# TelephoneConnect.net
KiCad netlist of a schematic drawn in EAGLE
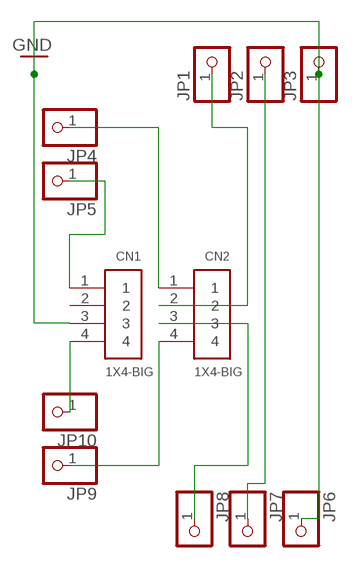
[diagram p0: schematic, sheet 1]

(export (version "E")
  (design (tool "Eeschema 10.0.6"))
  (components
    (comp (ref "CN1")
      (value "1X4-BIG")
      (footprint "eagle-import:1X04-BIG")
      (libsource (lib "eagle-import") (part "1X4-BIG"))
    )
    (comp (ref "CN2")
      (value "1X4-BIG")
      (footprint "eagle-import:1X04-BIG")
      (libsource (lib "eagle-import") (part "1X4-BIG"))
    )
    (comp (ref "JP1")
      (value "PINHD-1X1")
      (footprint "eagle-import:1X01")
      (libsource (lib "eagle-import") (part "PINHD-1X1"))
    )
    (comp (ref "JP2")
      (value "PINHD-1X1")
      (footprint "eagle-import:1X01")
      (libsource (lib "eagle-import") (part "PINHD-1X1"))
    )
    (comp (ref "JP3")
      (value "PINHD-1X1")
      (footprint "eagle-import:1X01")
      (libsource (lib "eagle-import") (part "PINHD-1X1"))
    )
    (comp (ref "JP4")
      (value "PINHD-1X1")
      (footprint "eagle-import:1X01")
      (libsource (lib "eagle-import") (part "PINHD-1X1"))
    )
    (comp (ref "JP5")
      (value "PINHD-1X1")
      (footprint "eagle-import:1X01")
      (libsource (lib "eagle-import") (part "PINHD-1X1"))
    )
    (comp (ref "JP6")
      (value "PINHD-1X1")
      (footprint "eagle-import:1X01")
      (libsource (lib "eagle-import") (part "PINHD-1X1"))
    )
    (comp (ref "JP7")
      (value "PINHD-1X1")
      (footprint "eagle-import:1X01")
      (libsource (lib "eagle-import") (part "PINHD-1X1"))
    )
    (comp (ref "JP8")
      (value "PINHD-1X1")
      (footprint "eagle-import:1X01")
      (libsource (lib "eagle-import") (part "PINHD-1X1"))
    )
    (comp (ref "JP9")
      (value "PINHD-1X1")
      (footprint "eagle-import:1X01")
      (libsource (lib "eagle-import") (part "PINHD-1X1"))
    )
    (comp (ref "JP10")
      (value "PINHD-1X1")
      (footprint "eagle-import:1X01")
      (libsource (lib "eagle-import") (part "PINHD-1X1"))
    )
  )
  (nets
    (net (code "1") (name "GND") (class "Default")
      (node (ref "CN1") (pin "3") (pinfunction "3_3") (pintype "bidirectional"))
      (node (ref "JP3") (pin "1") (pinfunction "1_1") (pintype "passive"))
      (node (ref "JP6") (pin "1") (pinfunction "1_1") (pintype "passive"))
    )
    (net (code "2") (name "Net-(CN1-Pad1)") (class "Default")
      (node (ref "CN1") (pin "1") (pinfunction "1_1") (pintype "bidirectional"))
      (node (ref "JP5") (pin "1") (pinfunction "1_1") (pintype "passive"))
    )
    (net (code "3") (name "Net-(CN1-Pad4)") (class "Default")
      (node (ref "CN1") (pin "4") (pinfunction "4_4") (pintype "bidirectional"))
      (node (ref "JP10") (pin "1") (pinfunction "1_1") (pintype "passive"))
    )
    (net (code "4") (name "Net-(CN2-Pad1)") (class "Default")
      (node (ref "CN2") (pin "1") (pinfunction "1_1") (pintype "bidirectional"))
      (node (ref "JP4") (pin "1") (pinfunction "1_1") (pintype "passive"))
    )
    (net (code "5") (name "Net-(CN2-Pad2)") (class "Default")
      (node (ref "CN2") (pin "2") (pinfunction "2_2") (pintype "bidirectional"))
      (node (ref "JP1") (pin "1") (pinfunction "1_1") (pintype "passive"))
    )
    (net (code "6") (name "Net-(CN2-Pad3)") (class "Default")
      (node (ref "CN2") (pin "3") (pinfunction "3_3") (pintype "bidirectional"))
      (node (ref "JP8") (pin "1") (pinfunction "1_1") (pintype "passive"))
    )
    (net (code "7") (name "Net-(CN2-Pad4)") (class "Default")
      (node (ref "CN2") (pin "4") (pinfunction "4_4") (pintype "bidirectional"))
      (node (ref "JP9") (pin "1") (pinfunction "1_1") (pintype "passive"))
    )
    (net (code "8") (name "Net-(JP2-Pad1)") (class "Default")
      (node (ref "JP2") (pin "1") (pinfunction "1_1") (pintype "passive"))
      (node (ref "JP7") (pin "1") (pinfunction "1_1") (pintype "passive"))
    )
    (net (code "9") (name "unconnected-(CN1-Pad2)") (class "Default")
      (node (ref "CN1") (pin "2") (pinfunction "2_2") (pintype "bidirectional"))
    )
  )
)
